# VaractorTline144Mhz.net
KiCad netlist of a schematic drawn in Altium Designer
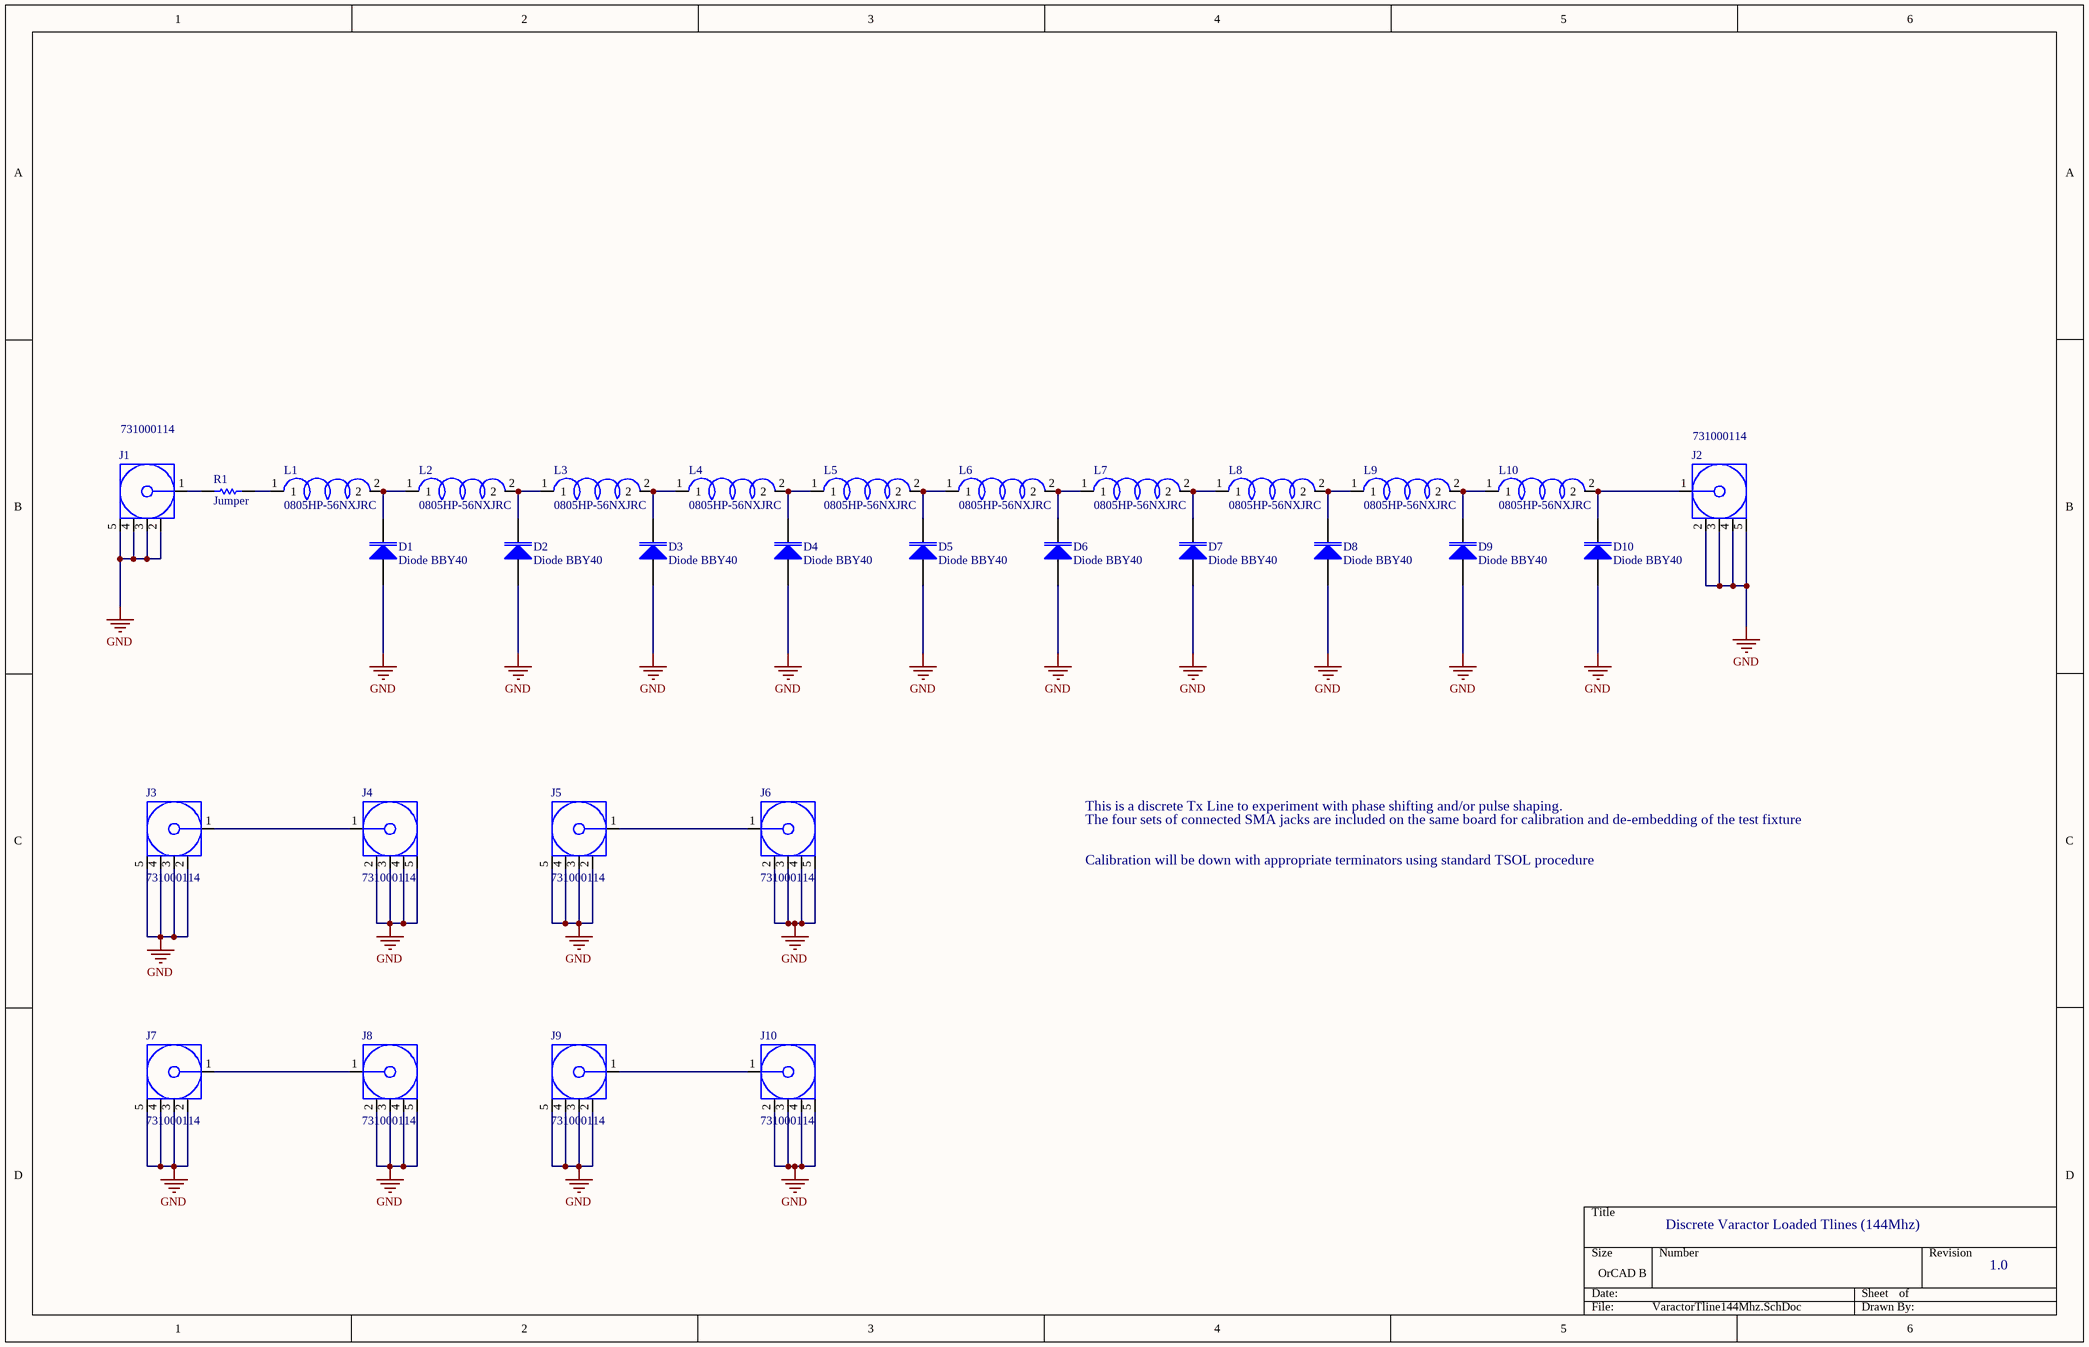
[diagram p0: VaractorTline144Mhz.SchDoc]

(export (version "E")
  (design (tool "Eeschema 10.0.6"))
  (components
    (comp (ref "D1")
      (value "Diode BBY40")
      (footprint "SOT23_N")
      (description "SOT23 Silicon Planar Variable Capacitance Diode")
      (fields (field (name "PUBLISHER") "Altium Limited"))
      (libsource (lib "Miscellaneous Devices") (part "Diode BBY40"))
    )
    (comp (ref "D2")
      (value "Diode BBY40")
      (footprint "SOT23_N")
      (description "SOT23 Silicon Planar Variable Capacitance Diode")
      (fields (field (name "PUBLISHER") "Altium Limited"))
      (libsource (lib "Miscellaneous Devices") (part "Diode BBY40"))
    )
    (comp (ref "D3")
      (value "Diode BBY40")
      (footprint "SOT23_N")
      (description "SOT23 Silicon Planar Variable Capacitance Diode")
      (fields (field (name "PUBLISHER") "Altium Limited"))
      (libsource (lib "Miscellaneous Devices") (part "Diode BBY40"))
    )
    (comp (ref "D4")
      (value "Diode BBY40")
      (footprint "SOT23_N")
      (description "SOT23 Silicon Planar Variable Capacitance Diode")
      (fields (field (name "PUBLISHER") "Altium Limited"))
      (libsource (lib "Miscellaneous Devices") (part "Diode BBY40"))
    )
    (comp (ref "D5")
      (value "Diode BBY40")
      (footprint "SOT23_N")
      (description "SOT23 Silicon Planar Variable Capacitance Diode")
      (fields (field (name "PUBLISHER") "Altium Limited"))
      (libsource (lib "Miscellaneous Devices") (part "Diode BBY40"))
    )
    (comp (ref "D6")
      (value "Diode BBY40")
      (footprint "SOT23_N")
      (description "SOT23 Silicon Planar Variable Capacitance Diode")
      (fields (field (name "PUBLISHER") "Altium Limited"))
      (libsource (lib "Miscellaneous Devices") (part "Diode BBY40"))
    )
    (comp (ref "D7")
      (value "Diode BBY40")
      (footprint "SOT23_N")
      (description "SOT23 Silicon Planar Variable Capacitance Diode")
      (fields (field (name "PUBLISHER") "Altium Limited"))
      (libsource (lib "Miscellaneous Devices") (part "Diode BBY40"))
    )
    (comp (ref "D8")
      (value "Diode BBY40")
      (footprint "SOT23_N")
      (description "SOT23 Silicon Planar Variable Capacitance Diode")
      (fields (field (name "PUBLISHER") "Altium Limited"))
      (libsource (lib "Miscellaneous Devices") (part "Diode BBY40"))
    )
    (comp (ref "D9")
      (value "Diode BBY40")
      (footprint "SOT23_N")
      (description "SOT23 Silicon Planar Variable Capacitance Diode")
      (fields (field (name "PUBLISHER") "Altium Limited"))
      (libsource (lib "Miscellaneous Devices") (part "Diode BBY40"))
    )
    (comp (ref "D10")
      (value "Diode BBY40")
      (footprint "SOT23_N")
      (description "SOT23 Silicon Planar Variable Capacitance Diode")
      (fields (field (name "PUBLISHER") "Altium Limited"))
      (libsource (lib "Miscellaneous Devices") (part "Diode BBY40"))
    )
    (comp (ref "J1")
      (value "731000114")
      (footprint "MOLX-731000114_V")
      (description "SMA Right-Angle PCB Jack Receptacle, Brass Body, Gold Plated, 50 Ohm, 5-Pin THD, RoHS, Tray")
      (fields (field (name "MANUFACTURER") "Molex"))
      (libsource (lib "Altium Content Vault") (part "CN-S-4F-RF5"))
    )
    (comp (ref "J2")
      (value "731000114")
      (footprint "MOLX-731000114_V")
      (description "SMA Right-Angle PCB Jack Receptacle, Brass Body, Gold Plated, 50 Ohm, 5-Pin THD, RoHS, Tray")
      (fields (field (name "MANUFACTURER") "Molex"))
      (libsource (lib "Altium Content Vault") (part "CN-S-4F-RF5"))
    )
    (comp (ref "J3")
      (value "731000114")
      (footprint "MOLX-731000114_V")
      (description "SMA Right-Angle PCB Jack Receptacle, Brass Body, Gold Plated, 50 Ohm, 5-Pin THD, RoHS, Tray")
      (fields (field (name "MANUFACTURER") "Molex"))
      (libsource (lib "Altium Content Vault") (part "CN-S-4F-RF5"))
    )
    (comp (ref "J4")
      (value "731000114")
      (footprint "MOLX-731000114_V")
      (description "SMA Right-Angle PCB Jack Receptacle, Brass Body, Gold Plated, 50 Ohm, 5-Pin THD, RoHS, Tray")
      (fields (field (name "MANUFACTURER") "Molex"))
      (libsource (lib "Altium Content Vault") (part "CN-S-4F-RF5"))
    )
    (comp (ref "J5")
      (value "731000114")
      (footprint "MOLX-731000114_V")
      (description "SMA Right-Angle PCB Jack Receptacle, Brass Body, Gold Plated, 50 Ohm, 5-Pin THD, RoHS, Tray")
      (fields (field (name "MANUFACTURER") "Molex"))
      (libsource (lib "Altium Content Vault") (part "CN-S-4F-RF5"))
    )
    (comp (ref "J6")
      (value "731000114")
      (footprint "MOLX-731000114_V")
      (description "SMA Right-Angle PCB Jack Receptacle, Brass Body, Gold Plated, 50 Ohm, 5-Pin THD, RoHS, Tray")
      (fields (field (name "MANUFACTURER") "Molex"))
      (libsource (lib "Altium Content Vault") (part "CN-S-4F-RF5"))
    )
    (comp (ref "J7")
      (value "731000114")
      (footprint "MOLX-731000114_V")
      (description "SMA Right-Angle PCB Jack Receptacle, Brass Body, Gold Plated, 50 Ohm, 5-Pin THD, RoHS, Tray")
      (fields (field (name "MANUFACTURER") "Molex"))
      (libsource (lib "Altium Content Vault") (part "CN-S-4F-RF5"))
    )
    (comp (ref "J8")
      (value "731000114")
      (footprint "MOLX-731000114_V")
      (description "SMA Right-Angle PCB Jack Receptacle, Brass Body, Gold Plated, 50 Ohm, 5-Pin THD, RoHS, Tray")
      (fields (field (name "MANUFACTURER") "Molex"))
      (libsource (lib "Altium Content Vault") (part "CN-S-4F-RF5"))
    )
    (comp (ref "J9")
      (value "731000114")
      (footprint "MOLX-731000114_V")
      (description "SMA Right-Angle PCB Jack Receptacle, Brass Body, Gold Plated, 50 Ohm, 5-Pin THD, RoHS, Tray")
      (fields (field (name "MANUFACTURER") "Molex"))
      (libsource (lib "Altium Content Vault") (part "CN-S-4F-RF5"))
    )
    (comp (ref "J10")
      (value "731000114")
      (footprint "MOLX-731000114_V")
      (description "SMA Right-Angle PCB Jack Receptacle, Brass Body, Gold Plated, 50 Ohm, 5-Pin THD, RoHS, Tray")
      (fields (field (name "MANUFACTURER") "Molex"))
      (libsource (lib "Altium Content Vault") (part "CN-S-4F-RF5"))
    )
    (comp (ref "L1")
      (value "0805HP-56NXJRC")
      (footprint "0805HQ SERIES")
      (description "0805HP-56NXJRC Coilcraft Variable Inductor")
      (fields (field (name "MANUFACTURER") "Coilcraft"))
      (libsource (lib "114MhzDiscreteTxline") (part "0805HP-56NXJRC"))
    )
    (comp (ref "L2")
      (value "0805HP-56NXJRC")
      (footprint "0805HQ SERIES")
      (description "0805HP-56NXJRC Coilcraft Variable Inductor")
      (fields (field (name "MANUFACTURER") "Coilcraft"))
      (libsource (lib "114MhzDiscreteTxline") (part "0805HP-56NXJRC"))
    )
    (comp (ref "L3")
      (value "0805HP-56NXJRC")
      (footprint "0805HQ SERIES")
      (description "0805HP-56NXJRC Coilcraft Variable Inductor")
      (fields (field (name "MANUFACTURER") "Coilcraft"))
      (libsource (lib "114MhzDiscreteTxline") (part "0805HP-56NXJRC"))
    )
    (comp (ref "L4")
      (value "0805HP-56NXJRC")
      (footprint "0805HQ SERIES")
      (description "0805HP-56NXJRC Coilcraft Variable Inductor")
      (fields (field (name "MANUFACTURER") "Coilcraft"))
      (libsource (lib "114MhzDiscreteTxline") (part "0805HP-56NXJRC"))
    )
    (comp (ref "L5")
      (value "0805HP-56NXJRC")
      (footprint "0805HQ SERIES")
      (description "0805HP-56NXJRC Coilcraft Variable Inductor")
      (fields (field (name "MANUFACTURER") "Coilcraft"))
      (libsource (lib "114MhzDiscreteTxline") (part "0805HP-56NXJRC"))
    )
    (comp (ref "L6")
      (value "0805HP-56NXJRC")
      (footprint "0805HQ SERIES")
      (description "0805HP-56NXJRC Coilcraft Variable Inductor")
      (fields (field (name "MANUFACTURER") "Coilcraft"))
      (libsource (lib "114MhzDiscreteTxline") (part "0805HP-56NXJRC"))
    )
    (comp (ref "L7")
      (value "0805HP-56NXJRC")
      (footprint "0805HQ SERIES")
      (description "0805HP-56NXJRC Coilcraft Variable Inductor")
      (fields (field (name "MANUFACTURER") "Coilcraft"))
      (libsource (lib "114MhzDiscreteTxline") (part "0805HP-56NXJRC"))
    )
    (comp (ref "L8")
      (value "0805HP-56NXJRC")
      (footprint "0805HQ SERIES")
      (description "0805HP-56NXJRC Coilcraft Variable Inductor")
      (fields (field (name "MANUFACTURER") "Coilcraft"))
      (libsource (lib "114MhzDiscreteTxline") (part "0805HP-56NXJRC"))
    )
    (comp (ref "L9")
      (value "0805HP-56NXJRC")
      (footprint "0805HQ SERIES")
      (description "0805HP-56NXJRC Coilcraft Variable Inductor")
      (fields (field (name "MANUFACTURER") "Coilcraft"))
      (libsource (lib "114MhzDiscreteTxline") (part "0805HP-56NXJRC"))
    )
    (comp (ref "L10")
      (value "0805HP-56NXJRC")
      (footprint "0805HQ SERIES")
      (description "0805HP-56NXJRC Coilcraft Variable Inductor")
      (fields (field (name "MANUFACTURER") "Coilcraft"))
      (libsource (lib "114MhzDiscreteTxline") (part "0805HP-56NXJRC"))
    )
    (comp (ref "R1")
      (value "Jumper")
      (footprint "RESC2013X70X40NL20T20")
      (description "Chip Resistor, 0 Ohm, +/- 1%, 0.125 W, -55 to 155 degC, 0805 (2012 Metric), RoHS, Tape and Reel")
      (fields (field (name "PARTNUMBER") "ERJ-6GEY0R00V") (field (name "TOLERANCE") "5%"))
      (libsource (lib "Altium Content Vault") (part "RES-2"))
    )
  )
  (nets
    (net (code "1") (name "GND") (class "Default")
      (node (ref "D1") (pin "3") (pinfunction "A_3") (pintype "passive"))
      (node (ref "D10") (pin "3") (pinfunction "A_3") (pintype "passive"))
      (node (ref "D2") (pin "3") (pinfunction "A_3") (pintype "passive"))
      (node (ref "D3") (pin "3") (pinfunction "A_3") (pintype "passive"))
      (node (ref "D4") (pin "3") (pinfunction "A_3") (pintype "passive"))
      (node (ref "D5") (pin "3") (pinfunction "A_3") (pintype "passive"))
      (node (ref "D6") (pin "3") (pinfunction "A_3") (pintype "passive"))
      (node (ref "D7") (pin "3") (pinfunction "A_3") (pintype "passive"))
      (node (ref "D8") (pin "3") (pinfunction "A_3") (pintype "passive"))
      (node (ref "D9") (pin "3") (pinfunction "A_3") (pintype "passive"))
      (node (ref "J1") (pin "2") (pinfunction "2_2") (pintype "passive"))
      (node (ref "J1") (pin "3") (pinfunction "3_3") (pintype "passive"))
      (node (ref "J1") (pin "4") (pinfunction "4_4") (pintype "passive"))
      (node (ref "J1") (pin "5") (pinfunction "5_5") (pintype "passive"))
      (node (ref "J10") (pin "2") (pinfunction "2_2") (pintype "passive"))
      (node (ref "J10") (pin "3") (pinfunction "3_3") (pintype "passive"))
      (node (ref "J10") (pin "4") (pinfunction "4_4") (pintype "passive"))
      (node (ref "J10") (pin "5") (pinfunction "5_5") (pintype "passive"))
      (node (ref "J2") (pin "2") (pinfunction "2_2") (pintype "passive"))
      (node (ref "J2") (pin "3") (pinfunction "3_3") (pintype "passive"))
      (node (ref "J2") (pin "4") (pinfunction "4_4") (pintype "passive"))
      (node (ref "J2") (pin "5") (pinfunction "5_5") (pintype "passive"))
      (node (ref "J3") (pin "2") (pinfunction "2_2") (pintype "passive"))
      (node (ref "J3") (pin "3") (pinfunction "3_3") (pintype "passive"))
      (node (ref "J3") (pin "4") (pinfunction "4_4") (pintype "passive"))
      (node (ref "J3") (pin "5") (pinfunction "5_5") (pintype "passive"))
      (node (ref "J4") (pin "2") (pinfunction "2_2") (pintype "passive"))
      (node (ref "J4") (pin "3") (pinfunction "3_3") (pintype "passive"))
      (node (ref "J4") (pin "4") (pinfunction "4_4") (pintype "passive"))
      (node (ref "J4") (pin "5") (pinfunction "5_5") (pintype "passive"))
      (node (ref "J5") (pin "2") (pinfunction "2_2") (pintype "passive"))
      (node (ref "J5") (pin "3") (pinfunction "3_3") (pintype "passive"))
      (node (ref "J5") (pin "4") (pinfunction "4_4") (pintype "passive"))
      (node (ref "J5") (pin "5") (pinfunction "5_5") (pintype "passive"))
      (node (ref "J6") (pin "2") (pinfunction "2_2") (pintype "passive"))
      (node (ref "J6") (pin "3") (pinfunction "3_3") (pintype "passive"))
      (node (ref "J6") (pin "4") (pinfunction "4_4") (pintype "passive"))
      (node (ref "J6") (pin "5") (pinfunction "5_5") (pintype "passive"))
      (node (ref "J7") (pin "2") (pinfunction "2_2") (pintype "passive"))
      (node (ref "J7") (pin "3") (pinfunction "3_3") (pintype "passive"))
      (node (ref "J7") (pin "4") (pinfunction "4_4") (pintype "passive"))
      (node (ref "J7") (pin "5") (pinfunction "5_5") (pintype "passive"))
      (node (ref "J8") (pin "2") (pinfunction "2_2") (pintype "passive"))
      (node (ref "J8") (pin "3") (pinfunction "3_3") (pintype "passive"))
      (node (ref "J8") (pin "4") (pinfunction "4_4") (pintype "passive"))
      (node (ref "J8") (pin "5") (pinfunction "5_5") (pintype "passive"))
      (node (ref "J9") (pin "2") (pinfunction "2_2") (pintype "passive"))
      (node (ref "J9") (pin "3") (pinfunction "3_3") (pintype "passive"))
      (node (ref "J9") (pin "4") (pinfunction "4_4") (pintype "passive"))
      (node (ref "J9") (pin "5") (pinfunction "5_5") (pintype "passive"))
    )
    (net (code "2") (name "Net-(D1-K)") (class "Default")
      (node (ref "D1") (pin "1") (pinfunction "K_1") (pintype "passive"))
      (node (ref "L1") (pin "2") (pinfunction "2_2") (pintype "passive"))
      (node (ref "L2") (pin "1") (pinfunction "1_1") (pintype "passive"))
    )
    (net (code "3") (name "Net-(D2-K)") (class "Default")
      (node (ref "D2") (pin "1") (pinfunction "K_1") (pintype "passive"))
      (node (ref "L2") (pin "2") (pinfunction "2_2") (pintype "passive"))
      (node (ref "L3") (pin "1") (pinfunction "1_1") (pintype "passive"))
    )
    (net (code "4") (name "Net-(D3-K)") (class "Default")
      (node (ref "D3") (pin "1") (pinfunction "K_1") (pintype "passive"))
      (node (ref "L3") (pin "2") (pinfunction "2_2") (pintype "passive"))
      (node (ref "L4") (pin "1") (pinfunction "1_1") (pintype "passive"))
    )
    (net (code "5") (name "Net-(D4-K)") (class "Default")
      (node (ref "D4") (pin "1") (pinfunction "K_1") (pintype "passive"))
      (node (ref "L4") (pin "2") (pinfunction "2_2") (pintype "passive"))
      (node (ref "L5") (pin "1") (pinfunction "1_1") (pintype "passive"))
    )
    (net (code "6") (name "Net-(D5-K)") (class "Default")
      (node (ref "D5") (pin "1") (pinfunction "K_1") (pintype "passive"))
      (node (ref "L5") (pin "2") (pinfunction "2_2") (pintype "passive"))
      (node (ref "L6") (pin "1") (pinfunction "1_1") (pintype "passive"))
    )
    (net (code "7") (name "Net-(D6-K)") (class "Default")
      (node (ref "D6") (pin "1") (pinfunction "K_1") (pintype "passive"))
      (node (ref "L6") (pin "2") (pinfunction "2_2") (pintype "passive"))
      (node (ref "L7") (pin "1") (pinfunction "1_1") (pintype "passive"))
    )
    (net (code "8") (name "Net-(D7-K)") (class "Default")
      (node (ref "D7") (pin "1") (pinfunction "K_1") (pintype "passive"))
      (node (ref "L7") (pin "2") (pinfunction "2_2") (pintype "passive"))
      (node (ref "L8") (pin "1") (pinfunction "1_1") (pintype "passive"))
    )
    (net (code "9") (name "Net-(D8-K)") (class "Default")
      (node (ref "D8") (pin "1") (pinfunction "K_1") (pintype "passive"))
      (node (ref "L8") (pin "2") (pinfunction "2_2") (pintype "passive"))
      (node (ref "L9") (pin "1") (pinfunction "1_1") (pintype "passive"))
    )
    (net (code "10") (name "Net-(D9-K)") (class "Default")
      (node (ref "D9") (pin "1") (pinfunction "K_1") (pintype "passive"))
      (node (ref "L10") (pin "1") (pinfunction "1_1") (pintype "passive"))
      (node (ref "L9") (pin "2") (pinfunction "2_2") (pintype "passive"))
    )
    (net (code "11") (name "Net-(D10-K)") (class "Default")
      (node (ref "D10") (pin "1") (pinfunction "K_1") (pintype "passive"))
      (node (ref "J2") (pin "1") (pinfunction "1_1") (pintype "passive"))
      (node (ref "L10") (pin "2") (pinfunction "2_2") (pintype "passive"))
    )
    (net (code "12") (name "Net-(J1-Pad1)") (class "Default")
      (node (ref "J1") (pin "1") (pinfunction "1_1") (pintype "passive"))
      (node (ref "R1") (pin "1") (pinfunction "1_1") (pintype "passive"))
    )
    (net (code "13") (name "Net-(J3-Pad1)") (class "Default")
      (node (ref "J3") (pin "1") (pinfunction "1_1") (pintype "passive"))
      (node (ref "J4") (pin "1") (pinfunction "1_1") (pintype "passive"))
    )
    (net (code "14") (name "Net-(J5-Pad1)") (class "Default")
      (node (ref "J5") (pin "1") (pinfunction "1_1") (pintype "passive"))
      (node (ref "J6") (pin "1") (pinfunction "1_1") (pintype "passive"))
    )
    (net (code "15") (name "Net-(J7-Pad1)") (class "Default")
      (node (ref "J7") (pin "1") (pinfunction "1_1") (pintype "passive"))
      (node (ref "J8") (pin "1") (pinfunction "1_1") (pintype "passive"))
    )
    (net (code "16") (name "Net-(J10-Pad1)") (class "Default")
      (node (ref "J10") (pin "1") (pinfunction "1_1") (pintype "passive"))
      (node (ref "J9") (pin "1") (pinfunction "1_1") (pintype "passive"))
    )
    (net (code "17") (name "Net-(L1-Pad1)") (class "Default")
      (node (ref "L1") (pin "1") (pinfunction "1_1") (pintype "passive"))
      (node (ref "R1") (pin "2") (pinfunction "2_2") (pintype "passive"))
    )
  )
)
